# main.net
KiCad netlist of a schematic drawn in Altium Designer
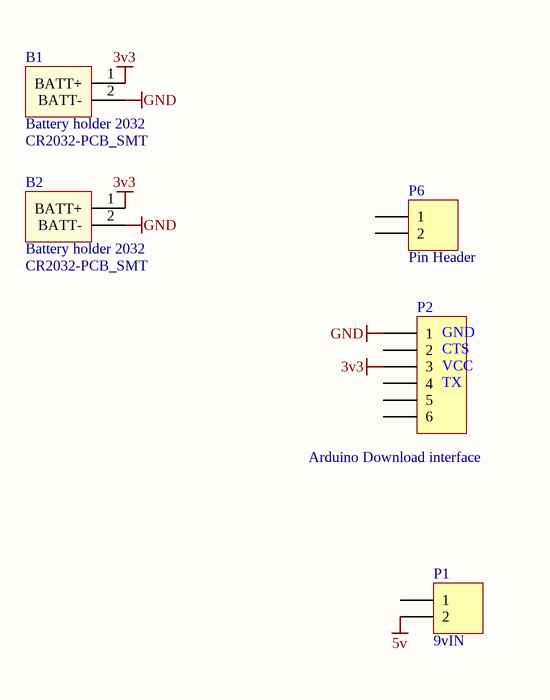
[diagram p0: main.SchDoc]

(export (version "E")
  (design (tool "Eeschema 10.0.6"))
  (components
    (comp (ref "B1")
      (value "Battery holder 2032")
      (footprint "CR2032_pcb_SMT")
      (description "BATTERY")
      (fields (field (name "PART NUMBER") "CR2032-PCB_SMT"))
      (libsource (lib "OurDb") (part "BATTERY"))
    )
    (comp (ref "B2")
      (value "Battery holder 2032")
      (footprint "CR2032_pcb_SMT")
      (description "BATTERY")
      (fields (field (name "PART NUMBER") "CR2032-PCB_SMT"))
      (libsource (lib "OurDb") (part "BATTERY"))
    )
    (comp (ref "P1")
      (value "9vIN")
      (footprint "PH1x2_2.54")
      (description "Con1x2")
      (fields (field (name "PART NUMBER") "PH1x2"))
      (libsource (lib "OurDb") (part "Con1x2"))
    )
    (comp (ref "P2")
      (value "Arduino Download interface")
      (footprint "PH1x6_2.54")
      (description "Con1x6")
      (fields (field (name "PART NUMBER") "PH1x6"))
      (libsource (lib "OurDb") (part "Con1x6"))
    )
    (comp (ref "P6")
      (value "Pin Header")
      (footprint "PH1x2_2.54")
      (description "Con1x2")
      (fields (field (name "PART NUMBER") "PH1x2") (field (name "AUTHOR") "Willy Pietersz"))
      (libsource (lib "OurDb") (part "Con1x2"))
    )
  )
  (nets
    (net (code "1") (name "3v3") (class "Default")
      (node (ref "B1") (pin "1") (pinfunction "BATT+_1") (pintype "passive"))
      (node (ref "B2") (pin "1") (pinfunction "BATT+_1") (pintype "passive"))
      (node (ref "P2") (pin "3") (pinfunction "3_3") (pintype "passive"))
    )
    (net (code "2") (name "5v") (class "Default")
      (node (ref "P1") (pin "2") (pinfunction "2_2") (pintype "passive"))
    )
    (net (code "3") (name "GND") (class "Default")
      (node (ref "B1") (pin "2") (pinfunction "BATT-_2") (pintype "power_in"))
      (node (ref "B2") (pin "2") (pinfunction "BATT-_2") (pintype "power_in"))
      (node (ref "P2") (pin "1") (pinfunction "1_1") (pintype "passive"))
    )
    (net (code "4") (name "unconnected-(P1-Pad1)") (class "Default")
      (node (ref "P1") (pin "1") (pinfunction "1_1") (pintype "passive"))
    )
    (net (code "5") (name "unconnected-(P2-Pad2)") (class "Default")
      (node (ref "P2") (pin "2") (pinfunction "2_2") (pintype "passive"))
    )
    (net (code "6") (name "unconnected-(P2-Pad4)") (class "Default")
      (node (ref "P2") (pin "4") (pinfunction "4_4") (pintype "passive"))
    )
    (net (code "7") (name "unconnected-(P2-Pad5)") (class "Default")
      (node (ref "P2") (pin "5") (pinfunction "5_5") (pintype "passive"))
    )
    (net (code "8") (name "unconnected-(P2-Pad6)") (class "Default")
      (node (ref "P2") (pin "6") (pinfunction "6_6") (pintype "passive"))
    )
    (net (code "9") (name "unconnected-(P6-Pad1)") (class "Default")
      (node (ref "P6") (pin "1") (pinfunction "1_1") (pintype "passive"))
    )
    (net (code "10") (name "unconnected-(P6-Pad2)") (class "Default")
      (node (ref "P6") (pin "2") (pinfunction "2_2") (pintype "passive"))
    )
  )
)
